# MIDImepower3.net
KiCad netlist of a schematic drawn in EAGLE
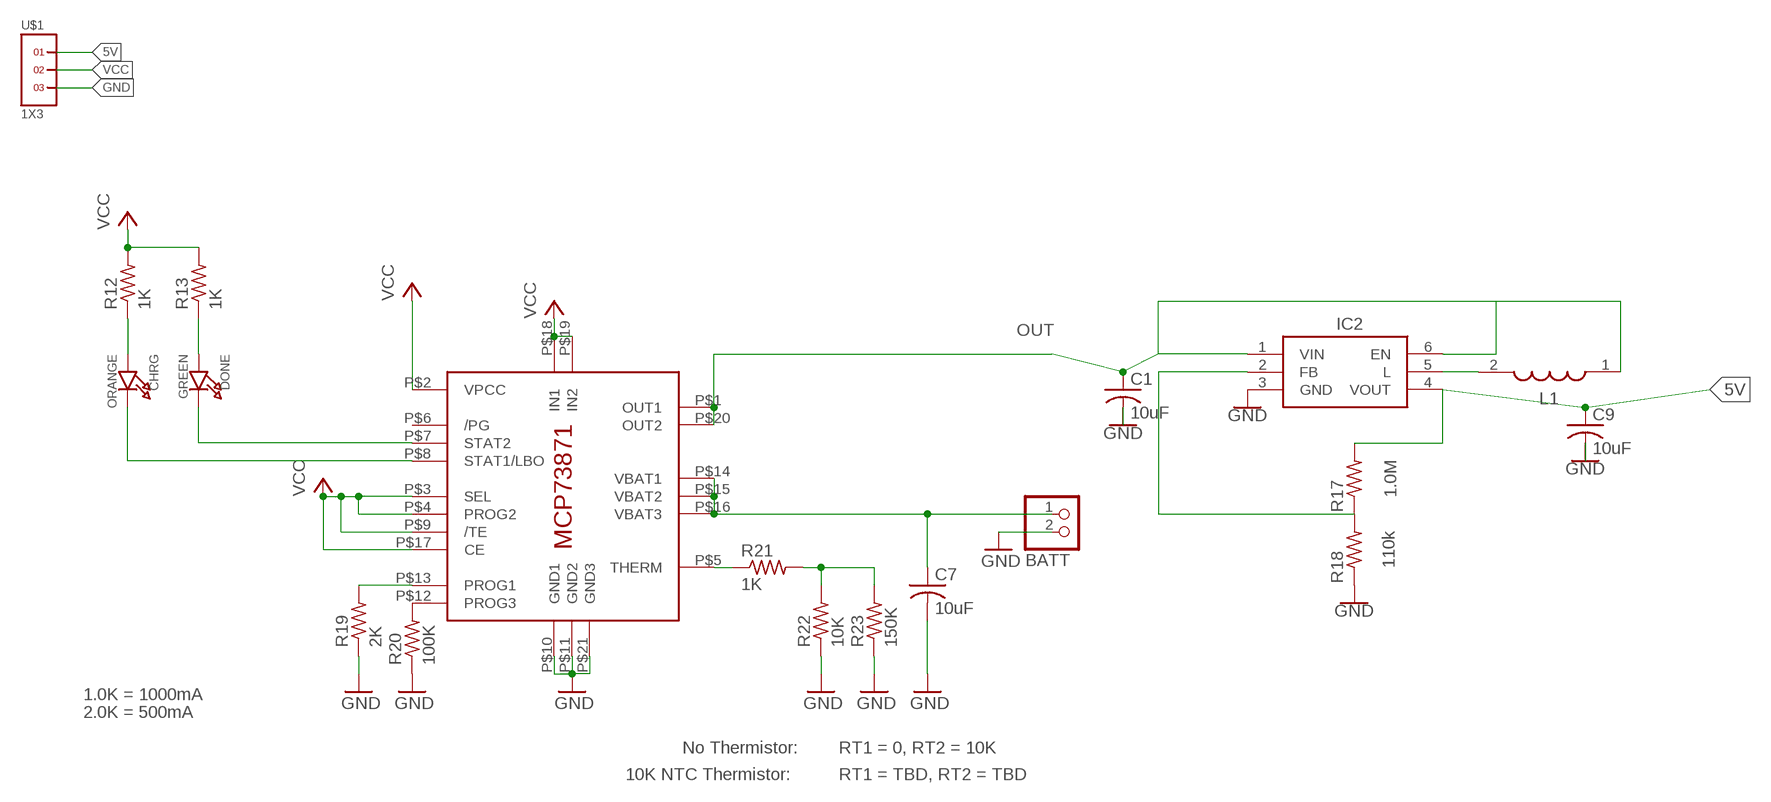
[diagram p0: schematic, sheet 1]

(export (version "E")
  (design (tool "Eeschema 10.0.6"))
  (components
    (comp (ref "BATT")
      (value "JST_2PIN-SMT-RA")
      (footprint "eagle-import:JST-PH-2-SMT-RA")
      (libsource (lib "eagle-import") (part "JST_2PIN-SMT-RA"))
    )
    (comp (ref "C1")
      (value "10uF")
      (footprint "eagle-import:C0805K")
      (libsource (lib "eagle-import") (part "C-USC0805K"))
    )
    (comp (ref "C7")
      (value "10uF")
      (footprint "eagle-import:C0805K")
      (libsource (lib "eagle-import") (part "C-USC0805K"))
    )
    (comp (ref "C9")
      (value "10uF")
      (footprint "eagle-import:C0805K")
      (libsource (lib "eagle-import") (part "C-USC0805K"))
    )
    (comp (ref "CHRG")
      (value "ORANGE")
      (footprint "eagle-import:CHIPLED_0805_NOOUTLINE")
      (libsource (lib "eagle-import") (part "LED0805_NOOUTLINE"))
    )
    (comp (ref "DONE")
      (value "GREEN")
      (footprint "eagle-import:CHIPLED_0805_NOOUTLINE")
      (libsource (lib "eagle-import") (part "LED0805_NOOUTLINE"))
    )
    (comp (ref "IC1")
      (value "MCP73871")
      (footprint "eagle-import:QFN20_4MM")
      (libsource (lib "eagle-import") (part "MCP73871"))
    )
    (comp (ref "IC2")
      (value "TPS61220DCKT")
      (footprint "eagle-import:SOT65P210X110-6N")
      (fields (field (name "MOUSER_PART_NUMBER") "595-TPS61220DCKT"))
      (libsource (lib "eagle-import") (part "TPS61220DCKT"))
    )
    (comp (ref "L1")
      (value "EPL3015-472MLC")
      (footprint "eagle-import:EPL3015472MLC")
      (fields (field (name "MOUSER_PART_NUMBER") "994-EPL3015-472MLC"))
      (libsource (lib "eagle-import") (part "EPL3015-472MLC"))
    )
    (comp (ref "R12")
      (value "1K")
      (footprint "eagle-import:R0402")
      (libsource (lib "eagle-import") (part "R-US_R0402"))
    )
    (comp (ref "R13")
      (value "1K")
      (footprint "eagle-import:R0402")
      (libsource (lib "eagle-import") (part "R-US_R0402"))
    )
    (comp (ref "R17")
      (value "1.0M")
      (footprint "eagle-import:R0402")
      (libsource (lib "eagle-import") (part "rcl_R-US_R0402"))
    )
    (comp (ref "R18")
      (value "110k")
      (footprint "eagle-import:R0402")
      (libsource (lib "eagle-import") (part "rcl_R-US_R0402"))
    )
    (comp (ref "R19")
      (value "2K")
      (footprint "eagle-import:R0402")
      (libsource (lib "eagle-import") (part "R-US_R0402"))
    )
    (comp (ref "R20")
      (value "100K")
      (footprint "eagle-import:R0402")
      (libsource (lib "eagle-import") (part "R-US_R0402"))
    )
    (comp (ref "R21")
      (value "1K")
      (footprint "eagle-import:R0402")
      (libsource (lib "eagle-import") (part "R-US_R0402"))
    )
    (comp (ref "R22")
      (value "10K")
      (footprint "eagle-import:R0402")
      (libsource (lib "eagle-import") (part "R-US_R0402"))
    )
    (comp (ref "R23")
      (value "150K")
      (footprint "eagle-import:R0402")
      (libsource (lib "eagle-import") (part "R-US_R0402"))
    )
    (comp (ref "U$1")
      (value "1X3")
      (footprint "eagle-import:1X3")
      (libsource (lib "eagle-import") (part "1X3"))
    )
  )
  (nets
    (net (code "1") (name "/OUT") (class "Default")
      (node (ref "C1") (pin "1") (pinfunction "1_1") (pintype "passive"))
      (node (ref "IC1") (pin "P$1") (pinfunction "OUT1_P$1") (pintype "output"))
      (node (ref "IC1") (pin "P$20") (pinfunction "OUT2_P$20") (pintype "output"))
      (node (ref "IC2") (pin "1") (pinfunction "VIN_1") (pintype "bidirectional"))
      (node (ref "IC2") (pin "6") (pinfunction "EN_6") (pintype "bidirectional"))
      (node (ref "L1") (pin "1") (pinfunction "1_1") (pintype "bidirectional"))
    )
    (net (code "2") (name "5V") (class "Default")
      (node (ref "C9") (pin "1") (pinfunction "1_1") (pintype "passive"))
      (node (ref "IC2") (pin "4") (pinfunction "VOUT_4") (pintype "bidirectional"))
      (node (ref "R17") (pin "2") (pinfunction "2_2") (pintype "passive"))
      (node (ref "U$1") (pin "1") (pinfunction "1_1") (pintype "bidirectional"))
    )
    (net (code "3") (name "GND") (class "Default")
      (node (ref "BATT") (pin "2") (pinfunction "1_2") (pintype "passive"))
      (node (ref "C1") (pin "2") (pinfunction "2_2") (pintype "passive"))
      (node (ref "C7") (pin "2") (pinfunction "2_2") (pintype "passive"))
      (node (ref "C9") (pin "2") (pinfunction "2_2") (pintype "passive"))
      (node (ref "IC1") (pin "P$10") (pinfunction "GND1_P$10") (pintype "power_in"))
      (node (ref "IC1") (pin "P$11") (pinfunction "GND2_P$11") (pintype "power_in"))
      (node (ref "IC1") (pin "P$21") (pinfunction "GND3_P$21") (pintype "power_in"))
      (node (ref "IC2") (pin "3") (pinfunction "GND_3") (pintype "bidirectional"))
      (node (ref "R18") (pin "1") (pinfunction "1_1") (pintype "passive"))
      (node (ref "R19") (pin "1") (pinfunction "1_1") (pintype "passive"))
      (node (ref "R20") (pin "1") (pinfunction "1_1") (pintype "passive"))
      (node (ref "R22") (pin "1") (pinfunction "1_1") (pintype "passive"))
      (node (ref "R23") (pin "1") (pinfunction "1_1") (pintype "passive"))
      (node (ref "U$1") (pin "3") (pinfunction "3_3") (pintype "bidirectional"))
    )
    (net (code "4") (name "Net-(BATT-2)") (class "Default")
      (node (ref "BATT") (pin "1") (pinfunction "2_1") (pintype "passive"))
      (node (ref "C7") (pin "1") (pinfunction "1_1") (pintype "passive"))
      (node (ref "IC1") (pin "P$14") (pinfunction "VBAT1_P$14") (pintype "output"))
      (node (ref "IC1") (pin "P$15") (pinfunction "VBAT2_P$15") (pintype "output"))
      (node (ref "IC1") (pin "P$16") (pinfunction "VBAT3_P$16") (pintype "output"))
    )
    (net (code "5") (name "Net-(CHRG-PadA)") (class "Default")
      (node (ref "CHRG") (pin "A") (pinfunction "A_A") (pintype "passive"))
      (node (ref "R12") (pin "1") (pinfunction "1_1") (pintype "passive"))
    )
    (net (code "6") (name "Net-(DONE-PadA)") (class "Default")
      (node (ref "DONE") (pin "A") (pinfunction "A_A") (pintype "passive"))
      (node (ref "R13") (pin "1") (pinfunction "1_1") (pintype "passive"))
    )
    (net (code "7") (name "Net-(IC1-PROG1)") (class "Default")
      (node (ref "IC1") (pin "P$13") (pinfunction "PROG1_P$13") (pintype "input"))
      (node (ref "R19") (pin "2") (pinfunction "2_2") (pintype "passive"))
    )
    (net (code "8") (name "Net-(IC1-PROG3)") (class "Default")
      (node (ref "IC1") (pin "P$12") (pinfunction "PROG3_P$12") (pintype "input"))
      (node (ref "R20") (pin "2") (pinfunction "2_2") (pintype "passive"))
    )
    (net (code "9") (name "Net-(IC1-STAT1{slash}LBO)") (class "Default")
      (node (ref "CHRG") (pin "C") (pinfunction "C_C") (pintype "passive"))
      (node (ref "IC1") (pin "P$8") (pinfunction "STAT1/LBO_P$8") (pintype "output"))
    )
    (net (code "10") (name "Net-(IC1-STAT2)") (class "Default")
      (node (ref "DONE") (pin "C") (pinfunction "C_C") (pintype "passive"))
      (node (ref "IC1") (pin "P$7") (pinfunction "STAT2_P$7") (pintype "output"))
    )
    (net (code "11") (name "Net-(IC1-THERM)") (class "Default")
      (node (ref "IC1") (pin "P$5") (pinfunction "THERM_P$5") (pintype "input"))
      (node (ref "R21") (pin "1") (pinfunction "1_1") (pintype "passive"))
    )
    (net (code "12") (name "Net-(IC2-FB)") (class "Default")
      (node (ref "IC2") (pin "2") (pinfunction "FB_2") (pintype "bidirectional"))
      (node (ref "R17") (pin "1") (pinfunction "1_1") (pintype "passive"))
      (node (ref "R18") (pin "2") (pinfunction "2_2") (pintype "passive"))
    )
    (net (code "13") (name "Net-(IC2-L)") (class "Default")
      (node (ref "IC2") (pin "5") (pinfunction "L_5") (pintype "bidirectional"))
      (node (ref "L1") (pin "2") (pinfunction "2_2") (pintype "bidirectional"))
    )
    (net (code "14") (name "Net-(R21-Pad2)") (class "Default")
      (node (ref "R21") (pin "2") (pinfunction "2_2") (pintype "passive"))
      (node (ref "R22") (pin "2") (pinfunction "2_2") (pintype "passive"))
      (node (ref "R23") (pin "2") (pinfunction "2_2") (pintype "passive"))
    )
    (net (code "15") (name "VCC") (class "Default")
      (node (ref "IC1") (pin "P$17") (pinfunction "CE_P$17") (pintype "input"))
      (node (ref "IC1") (pin "P$18") (pinfunction "IN1_P$18") (pintype "input"))
      (node (ref "IC1") (pin "P$19") (pinfunction "IN2_P$19") (pintype "input"))
      (node (ref "IC1") (pin "P$2") (pinfunction "VPCC_P$2") (pintype "input"))
      (node (ref "IC1") (pin "P$3") (pinfunction "SEL_P$3") (pintype "input"))
      (node (ref "IC1") (pin "P$4") (pinfunction "PROG2_P$4") (pintype "input"))
      (node (ref "IC1") (pin "P$9") (pinfunction "/TE_P$9") (pintype "input"))
      (node (ref "R12") (pin "2") (pinfunction "2_2") (pintype "passive"))
      (node (ref "R13") (pin "2") (pinfunction "2_2") (pintype "passive"))
      (node (ref "U$1") (pin "2") (pinfunction "2_2") (pintype "bidirectional"))
    )
    (net (code "16") (name "unconnected-(IC1-{slash}PG-PadP$6)") (class "Default")
      (node (ref "IC1") (pin "P$6") (pinfunction "/PG_P$6") (pintype "output"))
    )
  )
)
